# 10_TF.net
KiCad netlist of a schematic drawn in Altium Designer
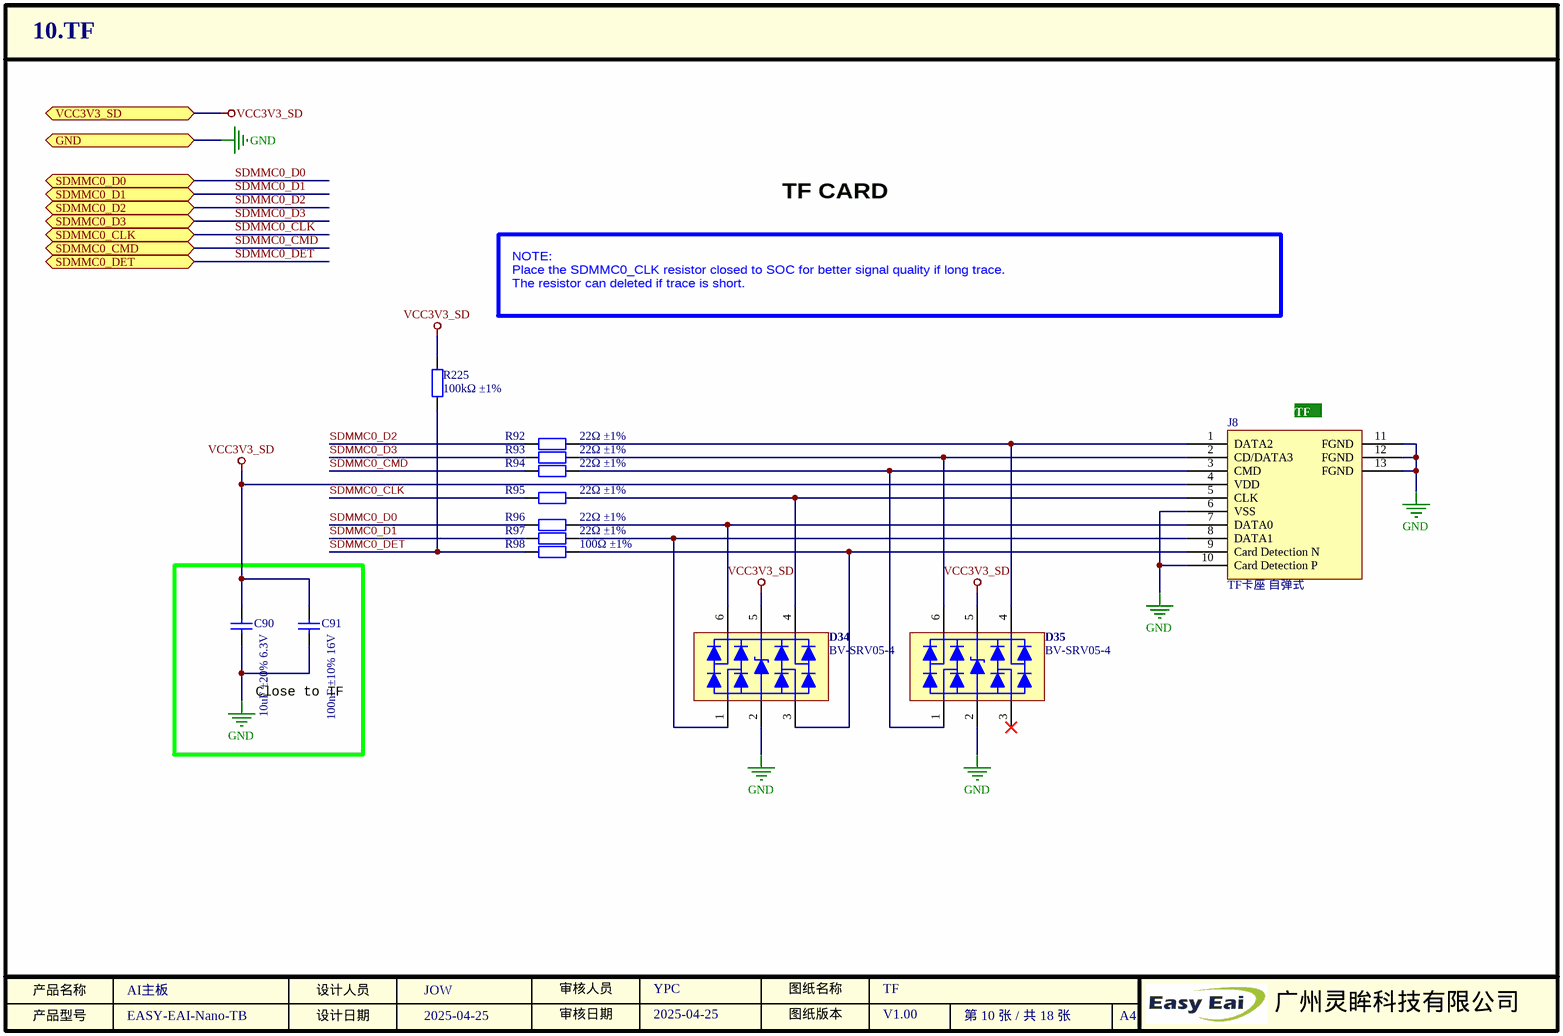
[diagram p0: 10.TF.SchDoc]

(export (version "E")
  (design (tool "Eeschema 10.0.6"))
  (components
    (comp (ref "C90")
      (value "CL05A106MQ5NUNC")
      (footprint "0402_C")
      (description "SPZL000269")
      (fields (field (name "描述") "10uF ±20% 6.3V"))
      (libsource (lib "CAP_lexing") (part "0402 10uF ±20% 6.3V"))
    )
    (comp (ref "C91")
      (value "CL05B104KO5NNNC")
      (footprint "0402_C")
      (description "SPZL000259")
      (fields (field (name "描述") "100nF ±10% 16V"))
      (libsource (lib "CAP_lexing") (part "0402 100nF ±10% 16V"))
    )
    (comp (ref "D34")
      (value "BV-SRV05-4")
      (footprint "SOT-23-6")
      (description "SPZL000615")
      (fields (field (name "型号") "BV-SRV05-4"))
      (libsource (lib "ESD_EASY-EAI") (part "ESD BV-SRV05-4"))
    )
    (comp (ref "D35")
      (value "BV-SRV05-4")
      (footprint "SOT-23-6")
      (description "SPZL000615")
      (fields (field (name "型号") "BV-SRV05-4"))
      (libsource (lib "ESD_EASY-EAI") (part "ESD BV-SRV05-4"))
    )
    (comp (ref "J8")
      (value "TF-01A")
      (footprint "TF")
      (description "SPZL000144")
      (fields (field (name "描述") "TF卡座 自弹式"))
      (libsource (lib "Connector_lexing") (part "TF卡座 自弹式"))
    )
    (comp (ref "R92")
      (value "0402WGF220JTCE")
      (footprint "0402_R")
      (description "SPZL000279")
      (fields (field (name "描述") "22Ω ±1%"))
      (libsource (lib "RES_lexing") (part "0402 22Ω ±1%"))
    )
    (comp (ref "R93")
      (value "0402WGF220JTCE")
      (footprint "0402_R")
      (description "SPZL000279")
      (fields (field (name "描述") "22Ω ±1%"))
      (libsource (lib "RES_lexing") (part "0402 22Ω ±1%"))
    )
    (comp (ref "R94")
      (value "0402WGF220JTCE")
      (footprint "0402_R")
      (description "SPZL000279")
      (fields (field (name "描述") "22Ω ±1%"))
      (libsource (lib "RES_lexing") (part "0402 22Ω ±1%"))
    )
    (comp (ref "R95")
      (value "0402WGF220JTCE")
      (footprint "0402_R")
      (description "SPZL000279")
      (fields (field (name "描述") "22Ω ±1%"))
      (libsource (lib "RES_lexing") (part "0402 22Ω ±1%"))
    )
    (comp (ref "R96")
      (value "0402WGF220JTCE")
      (footprint "0402_R")
      (description "SPZL000279")
      (fields (field (name "描述") "22Ω ±1%"))
      (libsource (lib "RES_lexing") (part "0402 22Ω ±1%"))
    )
    (comp (ref "R97")
      (value "0402WGF220JTCE")
      (footprint "0402_R")
      (description "SPZL000279")
      (fields (field (name "描述") "22Ω ±1%"))
      (libsource (lib "RES_lexing") (part "0402 22Ω ±1%"))
    )
    (comp (ref "R98")
      (value "0402WGF1000TCE")
      (footprint "0402_R")
      (description "SPZL000281")
      (fields (field (name "描述") "100Ω ±1%"))
      (libsource (lib "RES_lexing") (part "0402 100Ω ±1%"))
    )
    (comp (ref "R225")
      (value "0402WGF1003TCE")
      (footprint "0402_R")
      (description "SPZL000282")
      (fields (field (name "描述") "100kΩ ±1%"))
      (libsource (lib "RES_EASY-EAI") (part "0402 100kΩ ±1%"))
    )
  )
  (nets
    (net (code "1") (name "/SDMMC0_CLK") (class "Default")
      (node (ref "R95") (pin "1") (pinfunction "1_1") (pintype "passive"))
    )
    (net (code "2") (name "/SDMMC0_CMD") (class "Default")
      (node (ref "R94") (pin "1") (pinfunction "1_1") (pintype "passive"))
    )
    (net (code "3") (name "/SDMMC0_D0") (class "Default")
      (node (ref "R96") (pin "1") (pinfunction "1_1") (pintype "passive"))
    )
    (net (code "4") (name "/SDMMC0_D1") (class "Default")
      (node (ref "R97") (pin "1") (pinfunction "1_1") (pintype "passive"))
    )
    (net (code "5") (name "/SDMMC0_D2") (class "Default")
      (node (ref "R92") (pin "1") (pinfunction "1_1") (pintype "passive"))
    )
    (net (code "6") (name "/SDMMC0_D3") (class "Default")
      (node (ref "R93") (pin "1") (pinfunction "1_1") (pintype "passive"))
    )
    (net (code "7") (name "/SDMMC0_DET") (class "Default")
      (node (ref "R225") (pin "1") (pinfunction "1_1") (pintype "passive"))
      (node (ref "R98") (pin "1") (pinfunction "1_1") (pintype "passive"))
    )
    (net (code "8") (name "GND") (class "Default")
      (node (ref "C90") (pin "1") (pinfunction "1_1") (pintype "passive"))
      (node (ref "C91") (pin "1") (pinfunction "1_1") (pintype "passive"))
      (node (ref "D34") (pin "2") (pintype "passive"))
      (node (ref "D35") (pin "2") (pintype "passive"))
      (node (ref "J8") (pin "10") (pinfunction "Card_Detection_P_10") (pintype "passive"))
      (node (ref "J8") (pin "11") (pinfunction "FGND_11") (pintype "passive"))
      (node (ref "J8") (pin "12") (pinfunction "FGND_12") (pintype "passive"))
      (node (ref "J8") (pin "13") (pinfunction "FGND_13") (pintype "passive"))
      (node (ref "J8") (pin "6") (pinfunction "VSS_6") (pintype "passive"))
    )
    (net (code "9") (name "Net-(J8-CD{slash}DATA3)") (class "Default")
      (node (ref "D35") (pin "6") (pintype "passive"))
      (node (ref "J8") (pin "2") (pinfunction "CD/DATA3_2") (pintype "passive"))
      (node (ref "R93") (pin "2") (pinfunction "2_2") (pintype "passive"))
    )
    (net (code "10") (name "Net-(J8-CLK)") (class "Default")
      (node (ref "D34") (pin "4") (pintype "passive"))
      (node (ref "J8") (pin "5") (pinfunction "CLK_5") (pintype "passive"))
      (node (ref "R95") (pin "2") (pinfunction "2_2") (pintype "passive"))
    )
    (net (code "11") (name "Net-(J8-CMD)") (class "Default")
      (node (ref "D35") (pin "1") (pintype "passive"))
      (node (ref "J8") (pin "3") (pinfunction "CMD_3") (pintype "passive"))
      (node (ref "R94") (pin "2") (pinfunction "2_2") (pintype "passive"))
    )
    (net (code "12") (name "Net-(J8-Card_Detection_N)") (class "Default")
      (node (ref "D34") (pin "3") (pintype "passive"))
      (node (ref "J8") (pin "9") (pinfunction "Card_Detection_N_9") (pintype "passive"))
      (node (ref "R98") (pin "2") (pinfunction "2_2") (pintype "passive"))
    )
    (net (code "13") (name "Net-(J8-DATA0)") (class "Default")
      (node (ref "D34") (pin "6") (pintype "passive"))
      (node (ref "J8") (pin "7") (pinfunction "DATA0_7") (pintype "passive"))
      (node (ref "R96") (pin "2") (pinfunction "2_2") (pintype "passive"))
    )
    (net (code "14") (name "Net-(J8-DATA1)") (class "Default")
      (node (ref "D34") (pin "1") (pintype "passive"))
      (node (ref "J8") (pin "8") (pinfunction "DATA1_8") (pintype "passive"))
      (node (ref "R97") (pin "2") (pinfunction "2_2") (pintype "passive"))
    )
    (net (code "15") (name "Net-(J8-DATA2)") (class "Default")
      (node (ref "D35") (pin "4") (pintype "passive"))
      (node (ref "J8") (pin "1") (pinfunction "DATA2_1") (pintype "passive"))
      (node (ref "R92") (pin "2") (pinfunction "2_2") (pintype "passive"))
    )
    (net (code "16") (name "VCC3V3_SD") (class "Default")
      (node (ref "C90") (pin "2") (pinfunction "2_2") (pintype "passive"))
      (node (ref "C91") (pin "2") (pinfunction "2_2") (pintype "passive"))
      (node (ref "D34") (pin "5") (pintype "passive"))
      (node (ref "D35") (pin "5") (pintype "passive"))
      (node (ref "J8") (pin "4") (pinfunction "VDD_4") (pintype "passive"))
      (node (ref "R225") (pin "2") (pinfunction "2_2") (pintype "passive"))
    )
    (net (code "17") (name "unconnected-(D35-Pad3)") (class "Default")
      (node (ref "D35") (pin "3") (pintype "passive+no_connect"))
    )
  )
)
